# IR_Schreib_Lesekopf_TTL_Neu_V1.net
KiCad netlist of a schematic drawn in EAGLE
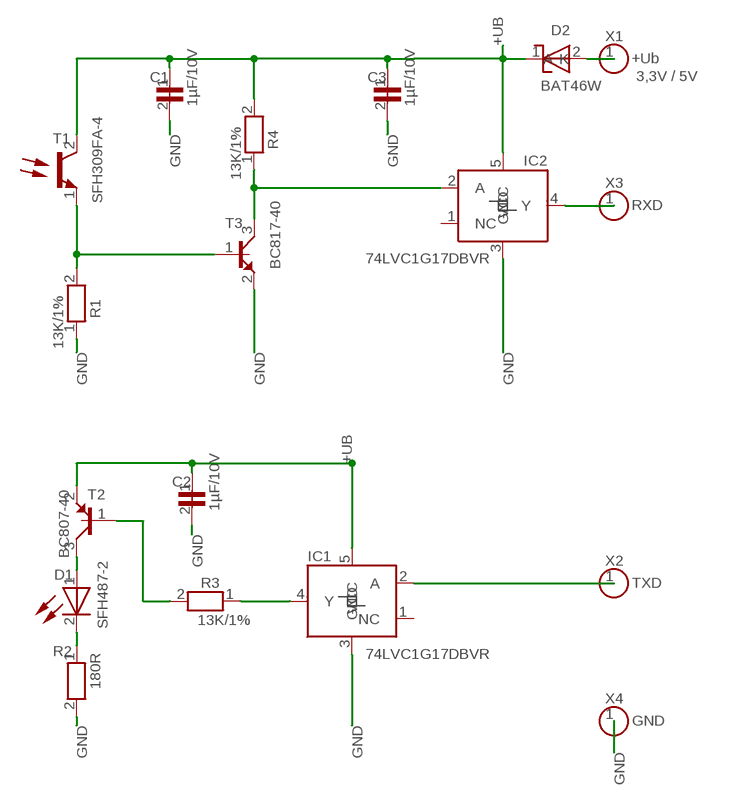
[diagram p0: schematic, sheet 1]

(export (version "E")
  (design (tool "Eeschema 10.0.6"))
  (components
    (comp (ref "C1")
      (value "1µF/10V")
      (footprint "eagle-import:0603")
      (libsource (lib "eagle-import") (part "1µF/10V"))
    )
    (comp (ref "C2")
      (value "1µF/10V")
      (footprint "eagle-import:0603")
      (libsource (lib "eagle-import") (part "1µF/10V"))
    )
    (comp (ref "C3")
      (value "1µF/10V")
      (footprint "eagle-import:0603")
      (libsource (lib "eagle-import") (part "1µF/10V"))
    )
    (comp (ref "D1")
      (value "SFH487-2")
      (footprint "eagle-import:LED_3MM")
      (libsource (lib "eagle-import") (part "SFH487-2"))
    )
    (comp (ref "D2")
      (value "BAT46W")
      (footprint "eagle-import:SOD123")
      (libsource (lib "eagle-import") (part "BAT46W"))
    )
    (comp (ref "IC1")
      (value "74LVC1G17DBVR")
      (footprint "eagle-import:SOT23_5")
      (libsource (lib "eagle-import") (part "74LVC1G17DBVR"))
    )
    (comp (ref "IC2")
      (value "74LVC1G17DBVR")
      (footprint "eagle-import:SOT23_5")
      (libsource (lib "eagle-import") (part "74LVC1G17DBVR"))
    )
    (comp (ref "R1")
      (value "13K/1%")
      (footprint "eagle-import:0603")
      (libsource (lib "eagle-import") (part "13K/1%"))
    )
    (comp (ref "R2")
      (value "180R")
      (footprint "eagle-import:0603")
      (libsource (lib "eagle-import") (part "180R"))
    )
    (comp (ref "R3")
      (value "13K/1%")
      (footprint "eagle-import:0603")
      (libsource (lib "eagle-import") (part "13K/1%"))
    )
    (comp (ref "R4")
      (value "13K/1%")
      (footprint "eagle-import:0603")
      (libsource (lib "eagle-import") (part "13K/1%"))
    )
    (comp (ref "T1")
      (value "SFH309FA-4")
      (footprint "eagle-import:LED_3MM")
      (libsource (lib "eagle-import") (part "SFH309FA-4"))
    )
    (comp (ref "T2")
      (value "BC807-40")
      (footprint "eagle-import:SOT23_3")
      (libsource (lib "eagle-import") (part "BC807-40"))
    )
    (comp (ref "T3")
      (value "BC817-40")
      (footprint "eagle-import:SOT23_3")
      (libsource (lib "eagle-import") (part "BC817-40"))
    )
    (comp (ref "X1")
      (value "+Ub")
      (footprint "eagle-import:LOETPUNKT")
      (libsource (lib "eagle-import") (part "+UB"))
    )
    (comp (ref "X2")
      (value "TXD")
      (footprint "eagle-import:LOETPUNKT")
      (libsource (lib "eagle-import") (part "TXD"))
    )
    (comp (ref "X3")
      (value "RXD")
      (footprint "eagle-import:LOETPUNKT")
      (libsource (lib "eagle-import") (part "RXD"))
    )
    (comp (ref "X4")
      (value "GND")
      (footprint "eagle-import:LOETPUNKT")
      (libsource (lib "eagle-import") (part "GND"))
    )
  )
  (nets
    (net (code "1") (name "/+UB") (class "Default")
      (node (ref "C1") (pin "1") (pinfunction "1_1") (pintype "passive"))
      (node (ref "C2") (pin "1") (pinfunction "1_1") (pintype "passive"))
      (node (ref "C3") (pin "1") (pinfunction "1_1") (pintype "passive"))
      (node (ref "D2") (pin "1") (pinfunction "K_1") (pintype "passive"))
      (node (ref "IC1") (pin "5") (pinfunction "VCC_5") (pintype "passive"))
      (node (ref "IC2") (pin "5") (pinfunction "VCC_5") (pintype "passive"))
      (node (ref "R4") (pin "2") (pinfunction "2_2") (pintype "passive"))
      (node (ref "T1") (pin "2") (pinfunction "2_2") (pintype "passive"))
      (node (ref "T2") (pin "2") (pinfunction "2_2") (pintype "passive"))
    )
    (net (code "2") (name "/GND") (class "Default")
      (node (ref "C1") (pin "2") (pinfunction "2_2") (pintype "passive"))
      (node (ref "C2") (pin "2") (pinfunction "2_2") (pintype "passive"))
      (node (ref "C3") (pin "2") (pinfunction "2_2") (pintype "passive"))
      (node (ref "IC1") (pin "3") (pinfunction "GND_3") (pintype "passive"))
      (node (ref "IC2") (pin "3") (pinfunction "GND_3") (pintype "passive"))
      (node (ref "R1") (pin "1") (pinfunction "1_1") (pintype "passive"))
      (node (ref "R2") (pin "2") (pinfunction "2_2") (pintype "passive"))
      (node (ref "T3") (pin "2") (pinfunction "2_2") (pintype "passive"))
      (node (ref "X4") (pin "1") (pinfunction "1_1") (pintype "passive"))
    )
    (net (code "3") (name "Net-(D1-Pad1)") (class "Default")
      (node (ref "D1") (pin "1") (pinfunction "1_1") (pintype "passive"))
      (node (ref "T2") (pin "3") (pinfunction "3_3") (pintype "passive"))
    )
    (net (code "4") (name "Net-(D1-Pad2)") (class "Default")
      (node (ref "D1") (pin "2") (pinfunction "2_2") (pintype "passive"))
      (node (ref "R2") (pin "1") (pinfunction "1_1") (pintype "passive"))
    )
    (net (code "5") (name "Net-(D2-A)") (class "Default")
      (node (ref "D2") (pin "2") (pinfunction "A_2") (pintype "passive"))
      (node (ref "X1") (pin "1") (pinfunction "1_1") (pintype "passive"))
    )
    (net (code "6") (name "Net-(IC1-A)") (class "Default")
      (node (ref "IC1") (pin "2") (pinfunction "A_2") (pintype "passive"))
      (node (ref "X2") (pin "1") (pinfunction "1_1") (pintype "passive"))
    )
    (net (code "7") (name "Net-(IC1-Y)") (class "Default")
      (node (ref "IC1") (pin "4") (pinfunction "Y_4") (pintype "passive"))
      (node (ref "R3") (pin "1") (pinfunction "1_1") (pintype "passive"))
    )
    (net (code "8") (name "Net-(IC2-A)") (class "Default")
      (node (ref "IC2") (pin "2") (pinfunction "A_2") (pintype "passive"))
      (node (ref "R4") (pin "1") (pinfunction "1_1") (pintype "passive"))
      (node (ref "T3") (pin "3") (pinfunction "3_3") (pintype "passive"))
    )
    (net (code "9") (name "Net-(IC2-Y)") (class "Default")
      (node (ref "IC2") (pin "4") (pinfunction "Y_4") (pintype "passive"))
      (node (ref "X3") (pin "1") (pinfunction "1_1") (pintype "passive"))
    )
    (net (code "10") (name "Net-(R1-Pad2)") (class "Default")
      (node (ref "R1") (pin "2") (pinfunction "2_2") (pintype "passive"))
      (node (ref "T1") (pin "1") (pinfunction "1_1") (pintype "passive"))
      (node (ref "T3") (pin "1") (pinfunction "1_1") (pintype "passive"))
    )
    (net (code "11") (name "Net-(R3-Pad2)") (class "Default")
      (node (ref "R3") (pin "2") (pinfunction "2_2") (pintype "passive"))
      (node (ref "T2") (pin "1") (pinfunction "1_1") (pintype "passive"))
    )
    (net (code "12") (name "unconnected-(IC1-NC-Pad1)") (class "Default")
      (node (ref "IC1") (pin "1") (pinfunction "NC_1") (pintype "passive"))
    )
    (net (code "13") (name "unconnected-(IC2-NC-Pad1)") (class "Default")
      (node (ref "IC2") (pin "1") (pinfunction "NC_1") (pintype "passive"))
    )
  )
)
